# POWER_2.net
KiCad netlist of a schematic drawn in Altium Designer
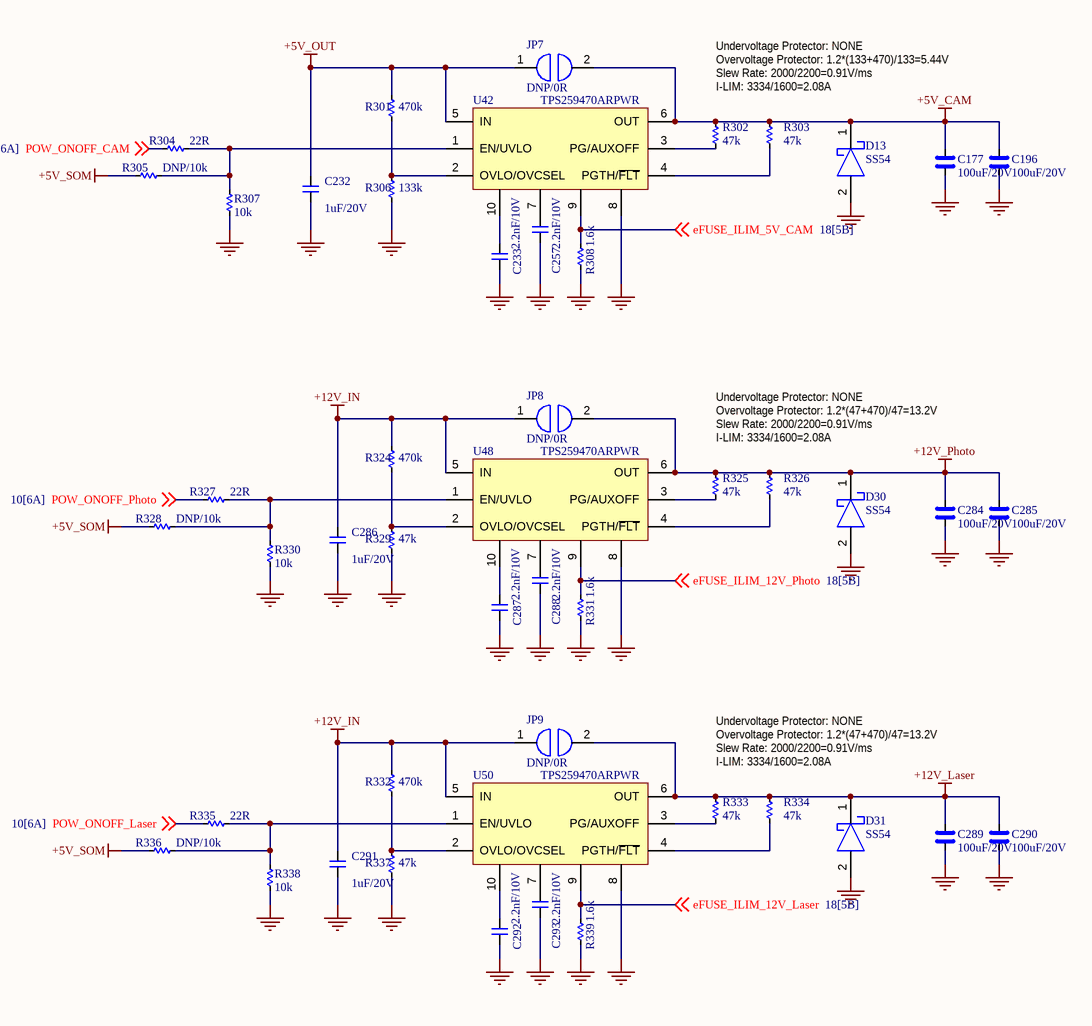
[diagram p0: POWER_2.SchDoc]

(export (version "E")
  (design (tool "Eeschema 10.0.6"))
  (components
    (comp (ref "C177")
      (value "100uF/20V")
      (footprint "CAP_C_3225X80")
      (description "CAP CHIP High Value")
      (libsource (lib "LABLIB") (part "_CAP_C_High_2"))
    )
    (comp (ref "C196")
      (value "100uF/20V")
      (footprint "CAP_C_3225X80")
      (description "CAP CHIP High Value")
      (libsource (lib "LABLIB") (part "_CAP_C_High_2"))
    )
    (comp (ref "C232")
      (value "1uF/20V")
      (footprint "CAP_C_1005X60")
      (description "CAP CHIP")
      (libsource (lib "LABLIB") (part "_CAP_C_2"))
    )
    (comp (ref "C233")
      (value "2.2nF/10V")
      (footprint "CAP_C_1005X60")
      (description "CAP CHIP")
      (libsource (lib "LABLIB") (part "_CAP_C_2"))
    )
    (comp (ref "C257")
      (value "2.2nF/10V")
      (footprint "CAP_C_1005X60")
      (description "CAP CHIP")
      (libsource (lib "LABLIB") (part "_CAP_C_2"))
    )
    (comp (ref "C284")
      (value "100uF/20V")
      (footprint "CAP_C_3225X80")
      (description "CAP CHIP High Value")
      (libsource (lib "LABLIB") (part "_CAP_C_High_2"))
    )
    (comp (ref "C285")
      (value "100uF/20V")
      (footprint "CAP_C_3225X80")
      (description "CAP CHIP High Value")
      (libsource (lib "LABLIB") (part "_CAP_C_High_2"))
    )
    (comp (ref "C286")
      (value "1uF/20V")
      (footprint "CAP_C_1005X60")
      (description "CAP CHIP")
      (libsource (lib "LABLIB") (part "_CAP_C_2"))
    )
    (comp (ref "C287")
      (value "2.2nF/10V")
      (footprint "CAP_C_1005X60")
      (description "CAP CHIP")
      (libsource (lib "LABLIB") (part "_CAP_C_2"))
    )
    (comp (ref "C288")
      (value "2.2nF/10V")
      (footprint "CAP_C_1005X60")
      (description "CAP CHIP")
      (libsource (lib "LABLIB") (part "_CAP_C_2"))
    )
    (comp (ref "C289")
      (value "100uF/20V")
      (footprint "CAP_C_3225X80")
      (description "CAP CHIP High Value")
      (libsource (lib "LABLIB") (part "_CAP_C_High_2"))
    )
    (comp (ref "C290")
      (value "100uF/20V")
      (footprint "CAP_C_3225X80")
      (description "CAP CHIP High Value")
      (libsource (lib "LABLIB") (part "_CAP_C_High_2"))
    )
    (comp (ref "C291")
      (value "1uF/20V")
      (footprint "CAP_C_1005X60")
      (description "CAP CHIP")
      (libsource (lib "LABLIB") (part "_CAP_C_2"))
    )
    (comp (ref "C292")
      (value "2.2nF/10V")
      (footprint "CAP_C_1005X60")
      (description "CAP CHIP")
      (libsource (lib "LABLIB") (part "_CAP_C_2"))
    )
    (comp (ref "C293")
      (value "2.2nF/10V")
      (footprint "CAP_C_1005X60")
      (description "CAP CHIP")
      (libsource (lib "LABLIB") (part "_CAP_C_2"))
    )
    (comp (ref "D13")
      (value "SS54")
      (footprint "DO-214AC_SMA")
      (description "DIODE SCHOTTKY 60V 3A DO214AA")
      (libsource (lib "EXP_HW_V3") (part "SS54"))
    )
    (comp (ref "D30")
      (value "SS54")
      (footprint "DO-214AC_SMA")
      (description "DIODE SCHOTTKY 60V 3A DO214AA")
      (libsource (lib "EXP_HW_V3") (part "SS54"))
    )
    (comp (ref "D31")
      (value "SS54")
      (footprint "DO-214AC_SMA")
      (description "DIODE SCHOTTKY 60V 3A DO214AA")
      (libsource (lib "EXP_HW_V3") (part "SS54"))
    )
    (comp (ref "JP7") (value "DNP/0R") (footprint "RES_C_1608X60") (libsource (lib "EXP_V1") (part "JUMPER")))
    (comp (ref "JP8") (value "DNP/0R") (footprint "RES_C_1608X60") (libsource (lib "EXP_V1") (part "JUMPER")))
    (comp (ref "JP9") (value "DNP/0R") (footprint "RES_C_1608X60") (libsource (lib "EXP_V1") (part "JUMPER")))
    (comp (ref "R301")
      (value "470k")
      (footprint "RES_C_1005X40")
      (description "RES")
      (libsource (lib "LABLIB") (part "_RES_B_2"))
    )
    (comp (ref "R302")
      (value "47k")
      (footprint "RES_C_1005X40")
      (description "RES")
      (libsource (lib "LABLIB") (part "_RES_B_2"))
    )
    (comp (ref "R303")
      (value "47k")
      (footprint "RES_C_1005X40")
      (description "RES")
      (libsource (lib "LABLIB") (part "_RES_B_2"))
    )
    (comp (ref "R304")
      (value "22R")
      (footprint "RES_C_1005X40")
      (description "RES")
      (libsource (lib "LABLIB") (part "_RES_B_2"))
    )
    (comp (ref "R305")
      (value "DNP/10k")
      (footprint "RES_C_1005X40")
      (description "RES")
      (libsource (lib "LABLIB") (part "_RES_B_2"))
    )
    (comp (ref "R306")
      (value "133k")
      (footprint "RES_C_1005X40")
      (description "RES")
      (libsource (lib "LABLIB") (part "_RES_B_2"))
    )
    (comp (ref "R307")
      (value "10k")
      (footprint "RES_C_1005X40")
      (description "RES")
      (libsource (lib "LABLIB") (part "_RES_B_2"))
    )
    (comp (ref "R308")
      (value "1.6k")
      (footprint "RES_C_1005X40")
      (description "RES")
      (libsource (lib "LABLIB") (part "_RES_B_2"))
    )
    (comp (ref "R324")
      (value "470k")
      (footprint "RES_C_1005X40")
      (description "RES")
      (libsource (lib "LABLIB") (part "_RES_B_2"))
    )
    (comp (ref "R325")
      (value "47k")
      (footprint "RES_C_1005X40")
      (description "RES")
      (libsource (lib "LABLIB") (part "_RES_B_2"))
    )
    (comp (ref "R326")
      (value "47k")
      (footprint "RES_C_1005X40")
      (description "RES")
      (libsource (lib "LABLIB") (part "_RES_B_2"))
    )
    (comp (ref "R327")
      (value "22R")
      (footprint "RES_C_1005X40")
      (description "RES")
      (libsource (lib "LABLIB") (part "_RES_B_2"))
    )
    (comp (ref "R328")
      (value "DNP/10k")
      (footprint "RES_C_1005X40")
      (description "RES")
      (libsource (lib "LABLIB") (part "_RES_B_2"))
    )
    (comp (ref "R329")
      (value "47k")
      (footprint "RES_C_1005X40")
      (description "RES")
      (libsource (lib "LABLIB") (part "_RES_B_2"))
    )
    (comp (ref "R330")
      (value "10k")
      (footprint "RES_C_1005X40")
      (description "RES")
      (libsource (lib "LABLIB") (part "_RES_B_2"))
    )
    (comp (ref "R331")
      (value "1.6k")
      (footprint "RES_C_1005X40")
      (description "RES")
      (libsource (lib "LABLIB") (part "_RES_B_2"))
    )
    (comp (ref "R332")
      (value "470k")
      (footprint "RES_C_1005X40")
      (description "RES")
      (libsource (lib "LABLIB") (part "_RES_B_2"))
    )
    (comp (ref "R333")
      (value "47k")
      (footprint "RES_C_1005X40")
      (description "RES")
      (libsource (lib "LABLIB") (part "_RES_B_2"))
    )
    (comp (ref "R334")
      (value "47k")
      (footprint "RES_C_1005X40")
      (description "RES")
      (libsource (lib "LABLIB") (part "_RES_B_2"))
    )
    (comp (ref "R335")
      (value "22R")
      (footprint "RES_C_1005X40")
      (description "RES")
      (libsource (lib "LABLIB") (part "_RES_B_2"))
    )
    (comp (ref "R336")
      (value "DNP/10k")
      (footprint "RES_C_1005X40")
      (description "RES")
      (libsource (lib "LABLIB") (part "_RES_B_2"))
    )
    (comp (ref "R337")
      (value "47k")
      (footprint "RES_C_1005X40")
      (description "RES")
      (libsource (lib "LABLIB") (part "_RES_B_2"))
    )
    (comp (ref "R338")
      (value "10k")
      (footprint "RES_C_1005X40")
      (description "RES")
      (libsource (lib "LABLIB") (part "_RES_B_2"))
    )
    (comp (ref "R339")
      (value "1.6k")
      (footprint "RES_C_1005X40")
      (description "RES")
      (libsource (lib "LABLIB") (part "_RES_B_2"))
    )
    (comp (ref "U42")
      (value "TPS259470ARPWR")
      (footprint "VQFN-HR-10")
      (libsource (lib "EXP_HW_V3") (part "TPS259470ARPWR"))
    )
    (comp (ref "U48")
      (value "TPS259470ARPWR")
      (footprint "VQFN-HR-10")
      (libsource (lib "EXP_HW_V3") (part "TPS259470ARPWR"))
    )
    (comp (ref "U50")
      (value "TPS259470ARPWR")
      (footprint "VQFN-HR-10")
      (libsource (lib "EXP_HW_V3") (part "TPS259470ARPWR"))
    )
  )
  (nets
    (net (code "1") (name "+5V_CAM") (class "Default")
      (node (ref "C177") (pin "2") (pinfunction "2_2") (pintype "passive"))
      (node (ref "C196") (pin "2") (pinfunction "2_2") (pintype "passive"))
      (node (ref "D13") (pin "1") (pinfunction "1_1") (pintype "passive"))
      (node (ref "JP7") (pin "2") (pinfunction "2_2") (pintype "passive"))
      (node (ref "R302") (pin "2") (pinfunction "2_2") (pintype "passive"))
      (node (ref "R303") (pin "2") (pinfunction "2_2") (pintype "passive"))
      (node (ref "U42") (pin "6") (pinfunction "OUT_6") (pintype "passive"))
    )
    (net (code "2") (name "+5V_OUT") (class "Default")
      (node (ref "C232") (pin "2") (pinfunction "2_2") (pintype "passive"))
      (node (ref "JP7") (pin "1") (pinfunction "1_1") (pintype "passive"))
      (node (ref "R301") (pin "2") (pinfunction "2_2") (pintype "passive"))
      (node (ref "U42") (pin "5") (pinfunction "IN_5") (pintype "passive"))
    )
    (net (code "3") (name "+5V_SOM") (class "Default")
      (node (ref "R305") (pin "2") (pinfunction "2_2") (pintype "passive"))
      (node (ref "R328") (pin "2") (pinfunction "2_2") (pintype "passive"))
      (node (ref "R336") (pin "2") (pinfunction "2_2") (pintype "passive"))
    )
    (net (code "4") (name "+12V_IN") (class "Default")
      (node (ref "C286") (pin "2") (pinfunction "2_2") (pintype "passive"))
      (node (ref "C291") (pin "2") (pinfunction "2_2") (pintype "passive"))
      (node (ref "JP8") (pin "1") (pinfunction "1_1") (pintype "passive"))
      (node (ref "JP9") (pin "1") (pinfunction "1_1") (pintype "passive"))
      (node (ref "R324") (pin "2") (pinfunction "2_2") (pintype "passive"))
      (node (ref "R332") (pin "2") (pinfunction "2_2") (pintype "passive"))
      (node (ref "U48") (pin "5") (pinfunction "IN_5") (pintype "passive"))
      (node (ref "U50") (pin "5") (pinfunction "IN_5") (pintype "passive"))
    )
    (net (code "5") (name "+12V_Laser") (class "Default")
      (node (ref "C289") (pin "2") (pinfunction "2_2") (pintype "passive"))
      (node (ref "C290") (pin "2") (pinfunction "2_2") (pintype "passive"))
      (node (ref "D31") (pin "1") (pinfunction "1_1") (pintype "passive"))
      (node (ref "JP9") (pin "2") (pinfunction "2_2") (pintype "passive"))
      (node (ref "R333") (pin "2") (pinfunction "2_2") (pintype "passive"))
      (node (ref "R334") (pin "2") (pinfunction "2_2") (pintype "passive"))
      (node (ref "U50") (pin "6") (pinfunction "OUT_6") (pintype "passive"))
    )
    (net (code "6") (name "+12V_Photo") (class "Default")
      (node (ref "C284") (pin "2") (pinfunction "2_2") (pintype "passive"))
      (node (ref "C285") (pin "2") (pinfunction "2_2") (pintype "passive"))
      (node (ref "D30") (pin "1") (pinfunction "1_1") (pintype "passive"))
      (node (ref "JP8") (pin "2") (pinfunction "2_2") (pintype "passive"))
      (node (ref "R325") (pin "2") (pinfunction "2_2") (pintype "passive"))
      (node (ref "R326") (pin "2") (pinfunction "2_2") (pintype "passive"))
      (node (ref "U48") (pin "6") (pinfunction "OUT_6") (pintype "passive"))
    )
    (net (code "7") (name "GND") (class "Default")
      (node (ref "C177") (pin "1") (pinfunction "1_1") (pintype "passive"))
      (node (ref "C196") (pin "1") (pinfunction "1_1") (pintype "passive"))
      (node (ref "C232") (pin "1") (pinfunction "1_1") (pintype "passive"))
      (node (ref "C233") (pin "1") (pinfunction "1_1") (pintype "passive"))
      (node (ref "C257") (pin "1") (pinfunction "1_1") (pintype "passive"))
      (node (ref "C284") (pin "1") (pinfunction "1_1") (pintype "passive"))
      (node (ref "C285") (pin "1") (pinfunction "1_1") (pintype "passive"))
      (node (ref "C286") (pin "1") (pinfunction "1_1") (pintype "passive"))
      (node (ref "C287") (pin "1") (pinfunction "1_1") (pintype "passive"))
      (node (ref "C288") (pin "1") (pinfunction "1_1") (pintype "passive"))
      (node (ref "C289") (pin "1") (pinfunction "1_1") (pintype "passive"))
      (node (ref "C290") (pin "1") (pinfunction "1_1") (pintype "passive"))
      (node (ref "C291") (pin "1") (pinfunction "1_1") (pintype "passive"))
      (node (ref "C292") (pin "1") (pinfunction "1_1") (pintype "passive"))
      (node (ref "C293") (pin "1") (pinfunction "1_1") (pintype "passive"))
      (node (ref "D13") (pin "2") (pinfunction "2_2") (pintype "passive"))
      (node (ref "D30") (pin "2") (pinfunction "2_2") (pintype "passive"))
      (node (ref "D31") (pin "2") (pinfunction "2_2") (pintype "passive"))
      (node (ref "R306") (pin "1") (pinfunction "1_1") (pintype "passive"))
      (node (ref "R307") (pin "2") (pinfunction "2_2") (pintype "passive"))
      (node (ref "R308") (pin "1") (pinfunction "1_1") (pintype "passive"))
      (node (ref "R329") (pin "1") (pinfunction "1_1") (pintype "passive"))
      (node (ref "R330") (pin "2") (pinfunction "2_2") (pintype "passive"))
      (node (ref "R331") (pin "1") (pinfunction "1_1") (pintype "passive"))
      (node (ref "R337") (pin "1") (pinfunction "1_1") (pintype "passive"))
      (node (ref "R338") (pin "2") (pinfunction "2_2") (pintype "passive"))
      (node (ref "R339") (pin "1") (pinfunction "1_1") (pintype "passive"))
      (node (ref "U42") (pin "8") (pinfunction "8_8") (pintype "passive"))
      (node (ref "U48") (pin "8") (pinfunction "8_8") (pintype "passive"))
      (node (ref "U50") (pin "8") (pinfunction "8_8") (pintype "passive"))
    )
    (net (code "8") (name "Net-(C233-Pad2)") (class "Default")
      (node (ref "C233") (pin "2") (pinfunction "2_2") (pintype "passive"))
      (node (ref "U42") (pin "10") (pinfunction "10_10") (pintype "passive"))
    )
    (net (code "9") (name "Net-(C257-Pad2)") (class "Default")
      (node (ref "C257") (pin "2") (pinfunction "2_2") (pintype "passive"))
      (node (ref "U42") (pin "7") (pinfunction "7_7") (pintype "passive"))
    )
    (net (code "10") (name "Net-(C287-Pad2)") (class "Default")
      (node (ref "C287") (pin "2") (pinfunction "2_2") (pintype "passive"))
      (node (ref "U48") (pin "10") (pinfunction "10_10") (pintype "passive"))
    )
    (net (code "11") (name "Net-(C288-Pad2)") (class "Default")
      (node (ref "C288") (pin "2") (pinfunction "2_2") (pintype "passive"))
      (node (ref "U48") (pin "7") (pinfunction "7_7") (pintype "passive"))
    )
    (net (code "12") (name "Net-(C292-Pad2)") (class "Default")
      (node (ref "C292") (pin "2") (pinfunction "2_2") (pintype "passive"))
      (node (ref "U50") (pin "10") (pinfunction "10_10") (pintype "passive"))
    )
    (net (code "13") (name "Net-(C293-Pad2)") (class "Default")
      (node (ref "C293") (pin "2") (pinfunction "2_2") (pintype "passive"))
      (node (ref "U50") (pin "7") (pinfunction "7_7") (pintype "passive"))
    )
    (net (code "14") (name "Net-(U42-EN{slash}UVLO)") (class "Default")
      (node (ref "R304") (pin "1") (pinfunction "1_1") (pintype "passive"))
      (node (ref "R305") (pin "1") (pinfunction "1_1") (pintype "passive"))
      (node (ref "R307") (pin "1") (pinfunction "1_1") (pintype "passive"))
      (node (ref "U42") (pin "1") (pinfunction "EN/UVLO_1") (pintype "passive"))
    )
    (net (code "15") (name "Net-(U42-OVLO{slash}OVCSEL)") (class "Default")
      (node (ref "R301") (pin "1") (pinfunction "1_1") (pintype "passive"))
      (node (ref "R306") (pin "2") (pinfunction "2_2") (pintype "passive"))
      (node (ref "U42") (pin "2") (pinfunction "OVLO/OVCSEL_2") (pintype "passive"))
    )
    (net (code "16") (name "Net-(U42-PGTH{slash}~{FLT})") (class "Default")
      (node (ref "R303") (pin "1") (pinfunction "1_1") (pintype "passive"))
      (node (ref "U42") (pin "4") (pinfunction "PGTH/~{FLT}_4") (pintype "passive"))
    )
    (net (code "17") (name "Net-(U42-PG{slash}AUXOFF)") (class "Default")
      (node (ref "R302") (pin "1") (pinfunction "1_1") (pintype "passive"))
      (node (ref "U42") (pin "3") (pinfunction "PG/AUXOFF_3") (pintype "passive"))
    )
    (net (code "18") (name "Net-(U48-EN{slash}UVLO)") (class "Default")
      (node (ref "R327") (pin "1") (pinfunction "1_1") (pintype "passive"))
      (node (ref "R328") (pin "1") (pinfunction "1_1") (pintype "passive"))
      (node (ref "R330") (pin "1") (pinfunction "1_1") (pintype "passive"))
      (node (ref "U48") (pin "1") (pinfunction "EN/UVLO_1") (pintype "passive"))
    )
    (net (code "19") (name "Net-(U48-OVLO{slash}OVCSEL)") (class "Default")
      (node (ref "R324") (pin "1") (pinfunction "1_1") (pintype "passive"))
      (node (ref "R329") (pin "2") (pinfunction "2_2") (pintype "passive"))
      (node (ref "U48") (pin "2") (pinfunction "OVLO/OVCSEL_2") (pintype "passive"))
    )
    (net (code "20") (name "Net-(U48-PGTH{slash}~{FLT})") (class "Default")
      (node (ref "R326") (pin "1") (pinfunction "1_1") (pintype "passive"))
      (node (ref "U48") (pin "4") (pinfunction "PGTH/~{FLT}_4") (pintype "passive"))
    )
    (net (code "21") (name "Net-(U48-PG{slash}AUXOFF)") (class "Default")
      (node (ref "R325") (pin "1") (pinfunction "1_1") (pintype "passive"))
      (node (ref "U48") (pin "3") (pinfunction "PG/AUXOFF_3") (pintype "passive"))
    )
    (net (code "22") (name "Net-(U50-EN{slash}UVLO)") (class "Default")
      (node (ref "R335") (pin "1") (pinfunction "1_1") (pintype "passive"))
      (node (ref "R336") (pin "1") (pinfunction "1_1") (pintype "passive"))
      (node (ref "R338") (pin "1") (pinfunction "1_1") (pintype "passive"))
      (node (ref "U50") (pin "1") (pinfunction "EN/UVLO_1") (pintype "passive"))
    )
    (net (code "23") (name "Net-(U50-OVLO{slash}OVCSEL)") (class "Default")
      (node (ref "R332") (pin "1") (pinfunction "1_1") (pintype "passive"))
      (node (ref "R337") (pin "2") (pinfunction "2_2") (pintype "passive"))
      (node (ref "U50") (pin "2") (pinfunction "OVLO/OVCSEL_2") (pintype "passive"))
    )
    (net (code "24") (name "Net-(U50-PGTH{slash}~{FLT})") (class "Default")
      (node (ref "R334") (pin "1") (pinfunction "1_1") (pintype "passive"))
      (node (ref "U50") (pin "4") (pinfunction "PGTH/~{FLT}_4") (pintype "passive"))
    )
    (net (code "25") (name "Net-(U50-PG{slash}AUXOFF)") (class "Default")
      (node (ref "R333") (pin "1") (pinfunction "1_1") (pintype "passive"))
      (node (ref "U50") (pin "3") (pinfunction "PG/AUXOFF_3") (pintype "passive"))
    )
    (net (code "26") (name "POW_ONOFF_CAM") (class "Default")
      (node (ref "R304") (pin "2") (pinfunction "2_2") (pintype "passive"))
    )
    (net (code "27") (name "POW_ONOFF_Laser") (class "Default")
      (node (ref "R335") (pin "2") (pinfunction "2_2") (pintype "passive"))
    )
    (net (code "28") (name "POW_ONOFF_Photo") (class "Default")
      (node (ref "R327") (pin "2") (pinfunction "2_2") (pintype "passive"))
    )
    (net (code "29") (name "eFUSE_ILIM_5V_CAM") (class "Default")
      (node (ref "R308") (pin "2") (pinfunction "2_2") (pintype "passive"))
      (node (ref "U42") (pin "9") (pinfunction "9_9") (pintype "passive"))
    )
    (net (code "30") (name "eFUSE_ILIM_12V_Laser") (class "Default")
      (node (ref "R339") (pin "2") (pinfunction "2_2") (pintype "passive"))
      (node (ref "U50") (pin "9") (pinfunction "9_9") (pintype "passive"))
    )
    (net (code "31") (name "eFUSE_ILIM_12V_Photo") (class "Default")
      (node (ref "R331") (pin "2") (pinfunction "2_2") (pintype "passive"))
      (node (ref "U48") (pin "9") (pinfunction "9_9") (pintype "passive"))
    )
  )
)
